# CC_microcontroleur.net
KiCad netlist of a schematic drawn in Altium Designer
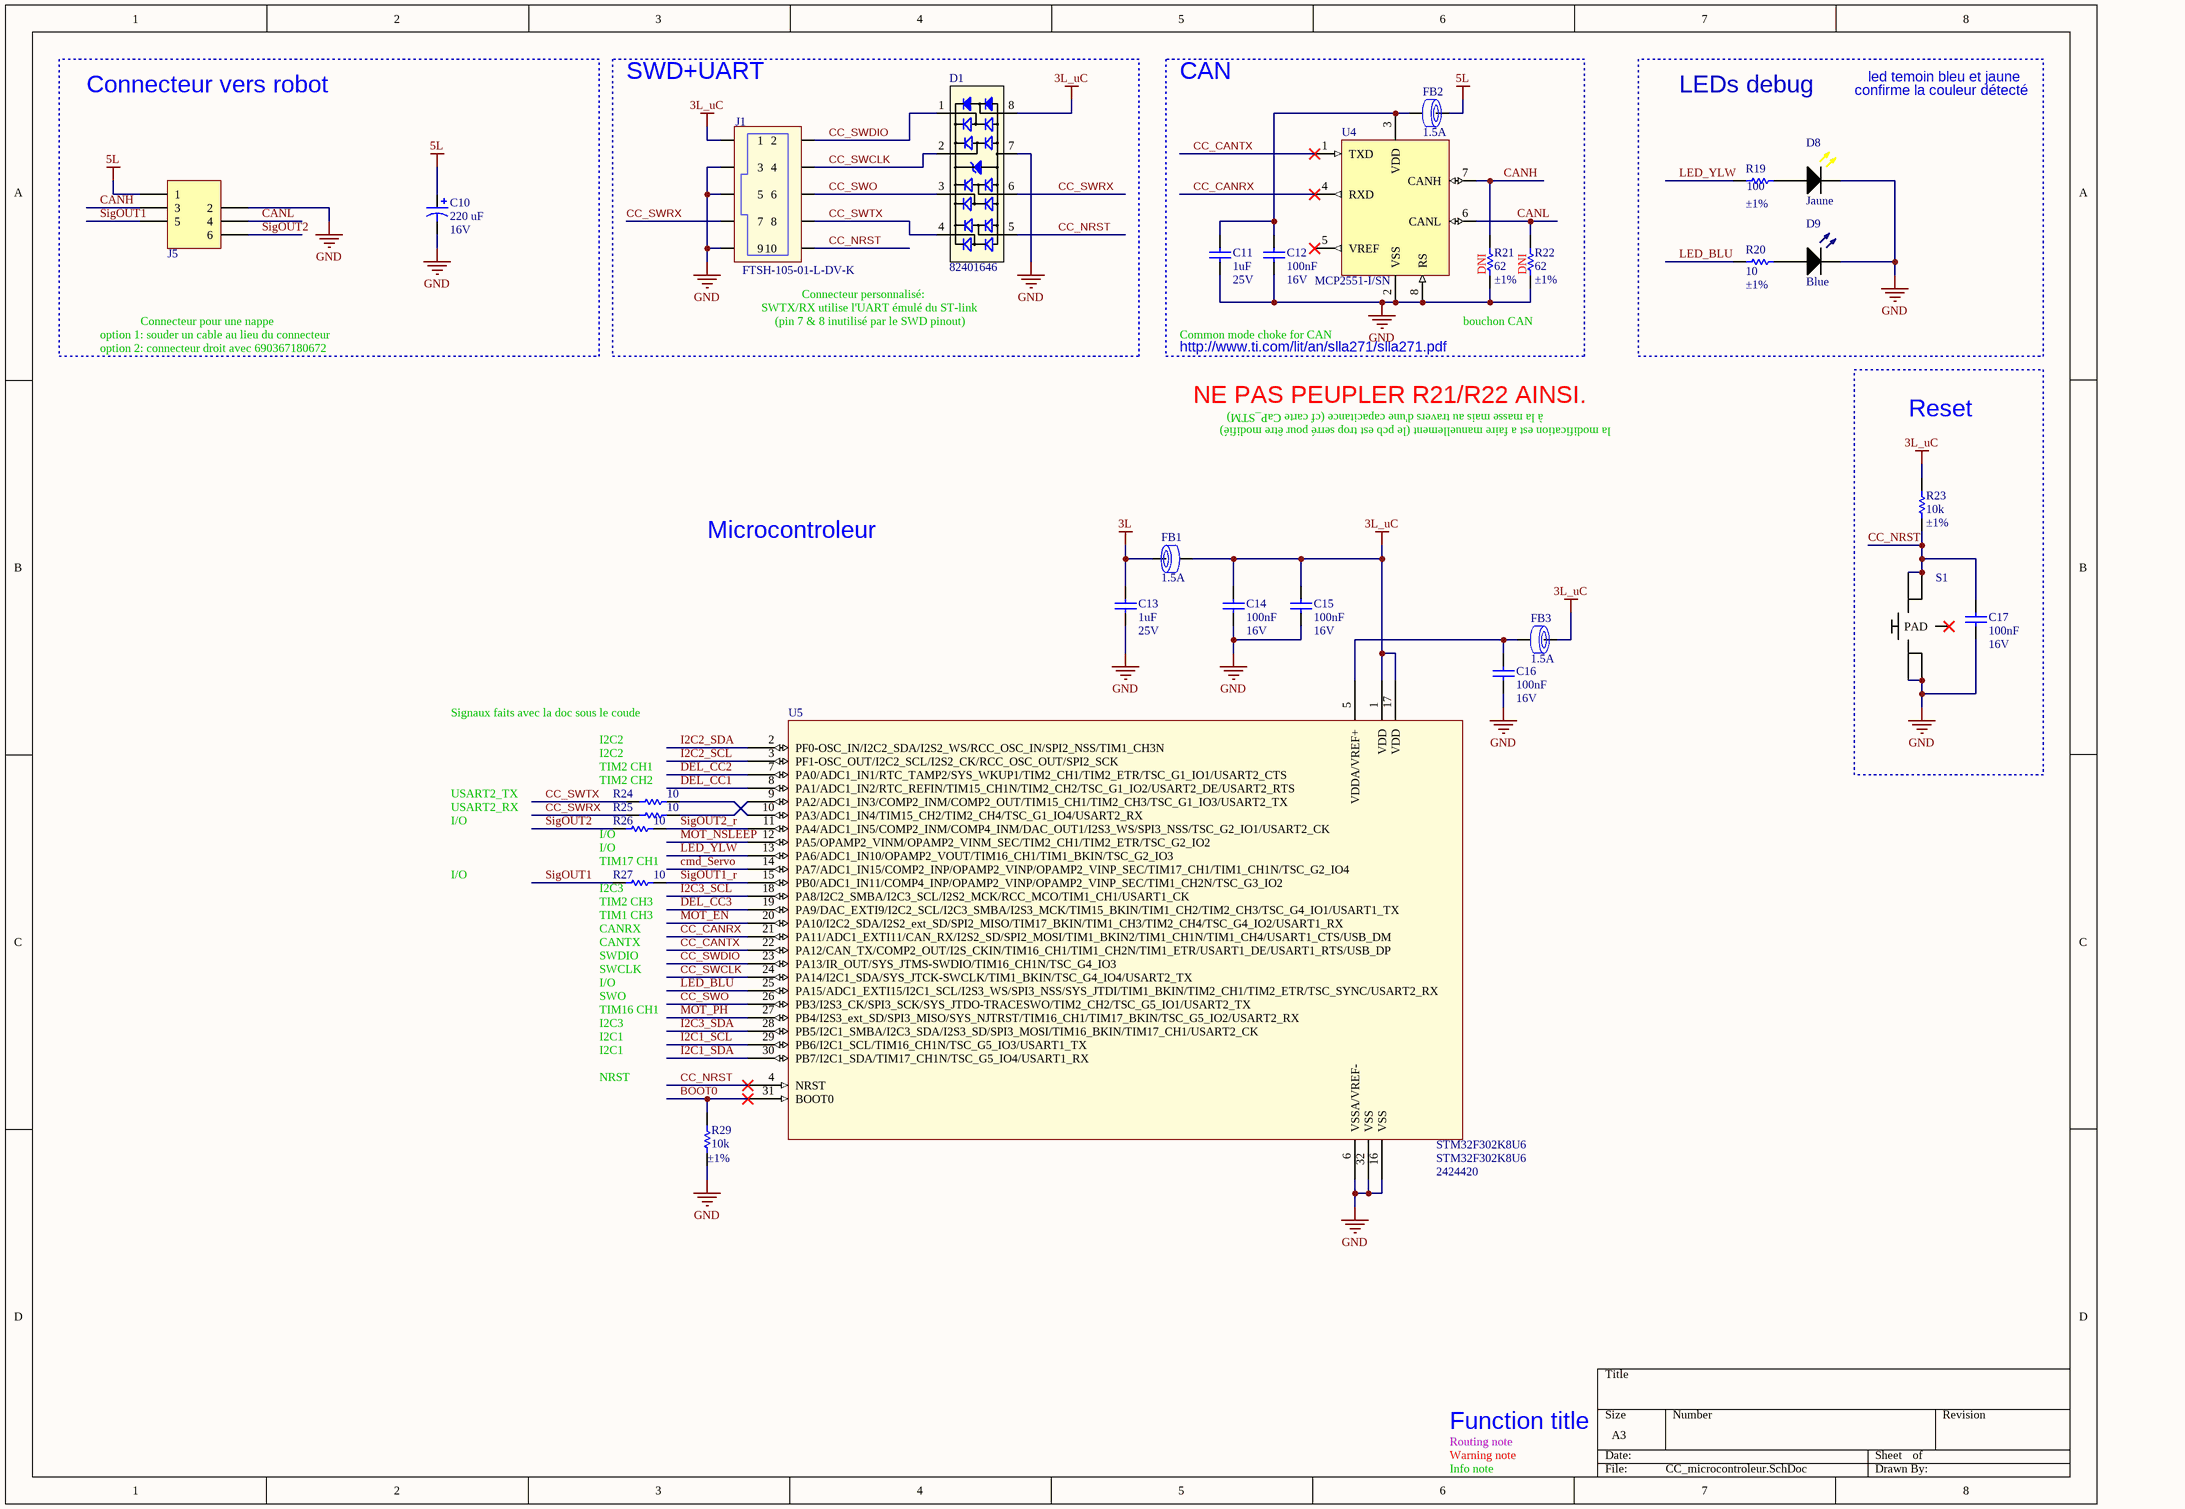
[diagram p0: CC_microcontroleur.SchDoc]

(export (version "E")
  (design (tool "Eeschema 10.0.6"))
  (components
    (comp (ref "C10")
      (value "220 uF")
      (footprint "WCAP-ATG8_6.3x11x2.5x0.5")
      (description "CAP Alu 220 UF 20% 16 V")
      (fields
        (field (name "MANUFACTURER") "Wurth Elektronik")
        (field (name "MANUFACTURER PART NUMBER") "860010373010")
        (field (name "RATEDVOLTAGE") "16V")
      )
      (libsource (lib "Condensateur") (part "WCAP-ATG8, 860010373010"))
    )
    (comp (ref "C11")
      (value "1uF")
      (footprint "WCAP-CSGP_0603, 1.6x0.8x0.8")
      (description "CAP CER 1uF 25V X7R 0603")
      (fields
        (field (name "MANUFACTURER") "Wurth Elektronik")
        (field (name "MANUFACTURER PART NUMBER") "885012206076")
        (field (name "RATEDVOLTAGE") "25V")
      )
      (libsource (lib "Condensateur") (part "WCAP-CSGP, 885012206076"))
    )
    (comp (ref "C12")
      (value "100nF")
      (footprint "WCAP-CSGP_0402, 1x0.5x0.5")
      (description "CAP CER 100nF 16V X7R 0402")
      (fields
        (field (name "RATEDVOLTAGE") "16V")
        (field (name "MANUFACTURER") "Wurth Elektronik")
        (field (name "MANUFACTURER PART NUMBER") "885012205037")
      )
      (libsource (lib "Condensateur") (part "WCAP-CSGP, 885012205037"))
    )
    (comp (ref "C13")
      (value "1uF")
      (footprint "WCAP-CSGP_0603, 1.6x0.8x0.8")
      (description "CAP CER 1uF 25V X7R 0603")
      (fields
        (field (name "MANUFACTURER") "Wurth Elektronik")
        (field (name "MANUFACTURER PART NUMBER") "885012206076")
        (field (name "RATEDVOLTAGE") "25V")
      )
      (libsource (lib "Condensateur") (part "WCAP-CSGP, 885012206076"))
    )
    (comp (ref "C14")
      (value "100nF")
      (footprint "WCAP-CSGP_0402, 1x0.5x0.5")
      (description "CAP CER 100nF 16V X7R 0402")
      (fields
        (field (name "RATEDVOLTAGE") "16V")
        (field (name "MANUFACTURER") "Wurth Elektronik")
        (field (name "MANUFACTURER PART NUMBER") "885012205037")
      )
      (libsource (lib "Condensateur") (part "WCAP-CSGP, 885012205037"))
    )
    (comp (ref "C15")
      (value "100nF")
      (footprint "WCAP-CSGP_0402, 1x0.5x0.5")
      (description "CAP CER 100nF 16V X7R 0402")
      (fields
        (field (name "RATEDVOLTAGE") "16V")
        (field (name "MANUFACTURER") "Wurth Elektronik")
        (field (name "MANUFACTURER PART NUMBER") "885012205037")
      )
      (libsource (lib "Condensateur") (part "WCAP-CSGP, 885012205037"))
    )
    (comp (ref "C16")
      (value "100nF")
      (footprint "WCAP-CSGP_0402, 1x0.5x0.5")
      (description "CAP CER 100nF 16V X7R 0402")
      (fields
        (field (name "RATEDVOLTAGE") "16V")
        (field (name "MANUFACTURER") "Wurth Elektronik")
        (field (name "MANUFACTURER PART NUMBER") "885012205037")
      )
      (libsource (lib "Condensateur") (part "WCAP-CSGP, 885012205037"))
    )
    (comp (ref "C17")
      (value "100nF")
      (footprint "WCAP-CSGP_0402, 1x0.5x0.5")
      (description "CAP CER 100nF 16V X7R 0402")
      (fields
        (field (name "MANUFACTURER") "Wurth Elektronik")
        (field (name "MANUFACTURER PART NUMBER") "885012205037")
        (field (name "RATEDVOLTAGE") "16V")
      )
      (libsource (lib "Condensateur") (part "WCAP-CSGP, 885012205037"))
    )
    (comp (ref "D1")
      (value "82401646")
      (footprint "MSOP-8L")
      (description "TVS DIODE 5VWM 13VC 8MSOP")
      (fields (field (name "MANUFACTURER") "Wurth Electronics Inc."))
      (libsource (lib "Diode") (part "82401646"))
    )
    (comp (ref "D8")
      (value "Jaune")
      (footprint "0603")
      (description "SMD mono-color Chip LED, WL-SMCW, Yellow")
      (fields
        (field (name "MANUFACTURER PART NUMBER") "150060YS75000")
        (field (name "CREATED BY") "Christin Otto")
      )
      (libsource (lib "Optoélectronique") (part "WL-SMCW 0603  150060YS75000"))
    )
    (comp (ref "D9")
      (value "Blue")
      (footprint "0603")
      (description "SMD mono-color Chip LED, WL-SMCW, Blue")
      (fields
        (field (name "MANUFACTURER PART NUMBER") "150060BS75000")
        (field (name "CREATED BY") "Christin Otto")
      )
      (libsource (lib "Optoélectronique") (part "WL-SMCW 0603  150060BS75000"))
    )
    (comp (ref "FB1")
      (value "742792624")
      (footprint "WE-CBF_0603_High Current")
      (description "Ferrite Bead 180ohm 0603 max1.5A")
      (fields (field (name "MANUFACTURER") "Wurth Elektronik") (field (name "RATEDCURRENT") "1.5A"))
      (libsource (lib "Inductance") (part "WE-CBF, 742792624"))
    )
    (comp (ref "FB2")
      (value "742792624")
      (footprint "WE-CBF_0603_High Current")
      (description "Ferrite Bead 180ohm 0603 max1.5A")
      (fields (field (name "MANUFACTURER") "Wurth Elektronik") (field (name "RATEDCURRENT") "1.5A"))
      (libsource (lib "Inductance") (part "WE-CBF, 742792624"))
    )
    (comp (ref "FB3")
      (value "742792624")
      (footprint "WE-CBF_0603_High Current")
      (description "Ferrite Bead 180ohm 0603 max1.5A")
      (fields (field (name "MANUFACTURER") "Wurth Elektronik") (field (name "RATEDCURRENT") "1.5A"))
      (libsource (lib "") (part "WE-CBF, 742792624_1"))
    )
    (comp (ref "J1")
      (value "FTSH-105-01-L-DV-K")
      (footprint "FTSH-105-01-L-DV-K")
      (description "CONN HEADER 10 POS DUAL .05\" SMD with Keying")
      (fields (field (name "MANUFACTURER") "Samtec Inc."))
      (libsource (lib "Connecteurs") (part "FTSH-105-01-L-DV-K"))
    )
    (comp (ref "J5")
      (value "690368170672")
      (footprint "690368170672")
      (description "WR-MM 6p Female Angled TH Connector with Polarization")
      (fields (field (name "MANUFACTURER") "Wurth Electronics Inc."))
      (libsource (lib "Connecteurs") (part "690368170672"))
    )
    (comp (ref "R19")
      (value "100")
      (footprint "RESC1005X04N")
      (description "RES SMD 100 OHM 1% 1/16W 0402")
      (fields
        (field (name "POWER") "63mW")
        (field (name "MANUFACTURER") "Yageo")
        (field (name "PRECISION") "±1%")
      )
      (libsource (lib "Resistance") (part "RC0402FR-07100RL"))
    )
    (comp (ref "R20")
      (value "10")
      (footprint "RESC1005X04N")
      (description "RES SMD 10 OHM 1% 1/16W 0402")
      (fields
        (field (name "POWER") "63mW")
        (field (name "MANUFACTURER") "Yageo")
        (field (name "PRECISION") "±1%")
      )
      (libsource (lib "Resistance") (part "RC0402FR-0710RL"))
    )
    (comp (ref "R21")
      (value "62")
      (footprint "RESC1005X04N")
      (description "RES SMD 62 OHM 1% 1/16W 0402")
      (fields
        (field (name "POWER") "63mW")
        (field (name "MANUFACTURER") "Yageo")
        (field (name "PRECISION") "±1%")
      )
      (libsource (lib "Resistance") (part "RC0402FR-0762RL"))
    )
    (comp (ref "R22")
      (value "62")
      (footprint "RESC1005X04N")
      (description "RES SMD 62 OHM 1% 1/16W 0402")
      (fields
        (field (name "POWER") "63mW")
        (field (name "MANUFACTURER") "Yageo")
        (field (name "PRECISION") "±1%")
      )
      (libsource (lib "Resistance") (part "RC0402FR-0762RL"))
    )
    (comp (ref "R23")
      (value "10k")
      (footprint "RESC1005X04N")
      (description "RES SMD 10K OHM 1% 1/16W 0402")
      (fields
        (field (name "POWER") "63mW")
        (field (name "MANUFACTURER") "Yageo")
        (field (name "PRECISION") "±1%")
      )
      (libsource (lib "Resistance") (part "RC0402FR-0710KL"))
    )
    (comp (ref "R24")
      (value "10")
      (footprint "RESC1005X04N")
      (description "RES SMD 10 OHM 1% 1/16W 0402")
      (fields (field (name "POWER") "63mW") (field (name "MANUFACTURER") "Yageo"))
      (libsource (lib "Resistance") (part "RC0402FR-0710RL"))
    )
    (comp (ref "R25")
      (value "10")
      (footprint "RESC1005X04N")
      (description "RES SMD 10 OHM 1% 1/16W 0402")
      (fields (field (name "POWER") "63mW") (field (name "MANUFACTURER") "Yageo"))
      (libsource (lib "Resistance") (part "RC0402FR-0710RL"))
    )
    (comp (ref "R26")
      (value "10")
      (footprint "RESC1005X04N")
      (description "RES SMD 10 OHM 1% 1/16W 0402")
      (fields (field (name "POWER") "63mW") (field (name "MANUFACTURER") "Yageo"))
      (libsource (lib "Resistance") (part "RC0402FR-0710RL"))
    )
    (comp (ref "R27")
      (value "10")
      (footprint "RESC1005X04N")
      (description "RES SMD 10 OHM 1% 1/16W 0402")
      (fields (field (name "POWER") "63mW") (field (name "MANUFACTURER") "Yageo"))
      (libsource (lib "Resistance") (part "RC0402FR-0710RL"))
    )
    (comp (ref "R29")
      (value "10k")
      (footprint "RESC1005X04N")
      (description "RES SMD 10K OHM 1% 1/16W 0402")
      (fields
        (field (name "POWER") "63mW")
        (field (name "MANUFACTURER") "Yageo")
        (field (name "PRECISION") "±1%")
      )
      (libsource (lib "Resistance") (part "RC0402FR-0710KL"))
    )
    (comp (ref "S1")
      (value "MCITPG")
      (footprint "MCIPTG23K-V")
      (description "Switch MCIPTG23K-V Multicomp")
      (fields
        (field (name "MANUFACTURER") "MULTICOMP")
        (field (name "MANUFACTURER PART NUMBER") "MCIPTG23K-V")
      )
      (libsource (lib "Switchs") (part "MCIPTG23K-V"))
    )
    (comp (ref "U4")
      (value "MCP2551-I/SN")
      (footprint "SO8_N")
      (description "IC TRANSCEIVER CAN HI-SPD 8-SOIC")
      (fields (field (name "MANUFACTURER") "Microchip Technology"))
      (libsource (lib "Serial") (part "MCP2551-I/SN"))
    )
    (comp (ref "U5")
      (value "STM32F302K8U6")
      (footprint "QFN50P500X500X60_HS-33N")
      (fields
        (field (name "MANUFACTURER") "STMICROELECTRONICS")
        (field (name "MANUFACTURER PART NUMBER") "STM32F302K8U6")
        (field (name "SUPPLIER PART NUMBER 1") "2424420")
      )
      (libsource (lib "Stm32") (part "STM32F302K8U6"))
    )
  )
  (nets
    (net (code "1") (name "/BOOT0") (class "Default")
      (node (ref "R29") (pin "2") (pinfunction "2_2") (pintype "passive"))
      (node (ref "U5") (pin "31") (pinfunction "BOOT0_31") (pintype "input"))
    )
    (net (code "2") (name "/CANH") (class "Default")
      (node (ref "J5") (pin "3") (pinfunction "3_3") (pintype "passive"))
      (node (ref "R21") (pin "2") (pinfunction "2_2") (pintype "passive"))
      (node (ref "U4") (pin "7") (pinfunction "CANH_7") (pintype "bidirectional"))
    )
    (net (code "3") (name "/CANL") (class "Default")
      (node (ref "J5") (pin "4") (pinfunction "4_4") (pintype "passive"))
      (node (ref "R22") (pin "2") (pinfunction "2_2") (pintype "passive"))
      (node (ref "U4") (pin "6") (pinfunction "CANL_6") (pintype "bidirectional"))
    )
    (net (code "4") (name "/CC_CANRX") (class "Default")
      (node (ref "U4") (pin "4") (pinfunction "RXD_4") (pintype "output"))
      (node (ref "U5") (pin "21") (pinfunction "PA11/ADC1_EXTI11/CAN_RX/I2S2_SD/SPI2_MOSI/TIM1_BKIN2/TIM1_CH1N/TIM1_CH4/USART1_CTS/USB_DM_21") (pintype "bidirectional"))
    )
    (net (code "5") (name "/CC_CANTX") (class "Default")
      (node (ref "U4") (pin "1") (pinfunction "TXD_1") (pintype "input"))
      (node (ref "U5") (pin "22") (pinfunction "PA12/CAN_TX/COMP2_OUT/I2S_CKIN/TIM16_CH1/TIM1_CH2N/TIM1_ETR/USART1_DE/USART1_RTS/USB_DP_22") (pintype "bidirectional"))
    )
    (net (code "6") (name "/CC_NRST") (class "Default")
      (node (ref "C17") (pin "2") (pinfunction "2_2") (pintype "passive"))
      (node (ref "D1") (pin "5") (pintype "passive"))
      (node (ref "J1") (pin "10") (pinfunction "10_10") (pintype "passive"))
      (node (ref "R23") (pin "1") (pinfunction "1_1") (pintype "passive"))
      (node (ref "S1") (pin "2") (pinfunction "2_2") (pintype "passive"))
      (node (ref "S1") (pin "4") (pinfunction "4_4") (pintype "passive"))
      (node (ref "U5") (pin "4") (pinfunction "NRST_4") (pintype "input"))
    )
    (net (code "7") (name "/CC_SWCLK") (class "Default")
      (node (ref "D1") (pin "2") (pintype "passive"))
      (node (ref "J1") (pin "4") (pinfunction "4_4") (pintype "passive"))
      (node (ref "U5") (pin "24") (pinfunction "PA14/I2C1_SDA/SYS_JTCK-SWCLK/TIM1_BKIN/TSC_G4_IO4/USART2_TX_24") (pintype "bidirectional"))
    )
    (net (code "8") (name "/CC_SWDIO") (class "Default")
      (node (ref "D1") (pin "1") (pintype "passive"))
      (node (ref "J1") (pin "2") (pinfunction "2_2") (pintype "passive"))
      (node (ref "U5") (pin "23") (pinfunction "PA13/IR_OUT/SYS_JTMS-SWDIO/TIM16_CH1N/TSC_G4_IO3_23") (pintype "bidirectional"))
    )
    (net (code "9") (name "/CC_SWO") (class "Default")
      (node (ref "D1") (pin "3") (pintype "passive"))
      (node (ref "J1") (pin "6") (pinfunction "6_6") (pintype "passive"))
      (node (ref "U5") (pin "26") (pinfunction "PB3/I2S3_CK/SPI3_SCK/SYS_JTDO-TRACESWO/TIM2_CH2/TSC_G5_IO1/USART2_TX_26") (pintype "bidirectional"))
    )
    (net (code "10") (name "/CC_SWRX") (class "Default")
      (node (ref "D1") (pin "6") (pintype "passive"))
      (node (ref "J1") (pin "7") (pinfunction "7_7") (pintype "passive"))
      (node (ref "R25") (pin "1") (pinfunction "1_1") (pintype "passive"))
    )
    (net (code "11") (name "/CC_SWTX") (class "Default")
      (node (ref "D1") (pin "4") (pintype "passive"))
      (node (ref "J1") (pin "8") (pinfunction "8_8") (pintype "passive"))
      (node (ref "R24") (pin "1") (pinfunction "1_1") (pintype "passive"))
    )
    (net (code "12") (name "/DEL_CC1") (class "Default")
      (node (ref "U5") (pin "8") (pinfunction "PA1/ADC1_IN2/RTC_REFIN/TIM15_CH1N/TIM2_CH2/TSC_G1_IO2/USART2_DE/USART2_RTS_8") (pintype "bidirectional"))
    )
    (net (code "13") (name "/DEL_CC2") (class "Default")
      (node (ref "U5") (pin "7") (pinfunction "PA0/ADC1_IN1/RTC_TAMP2/SYS_WKUP1/TIM2_CH1/TIM2_ETR/TSC_G1_IO1/USART2_CTS_7") (pintype "bidirectional"))
    )
    (net (code "14") (name "/DEL_CC3") (class "Default")
      (node (ref "U5") (pin "19") (pinfunction "PA9/DAC_EXTI9/I2C2_SCL/I2C3_SMBA/I2S3_MCK/TIM15_BKIN/TIM1_CH2/TIM2_CH3/TSC_G4_IO1/USART1_TX_19") (pintype "bidirectional"))
    )
    (net (code "15") (name "/I2C1_SCL") (class "Default")
      (node (ref "U5") (pin "29") (pinfunction "PB6/I2C1_SCL/TIM16_CH1N/TSC_G5_IO3/USART1_TX_29") (pintype "bidirectional"))
    )
    (net (code "16") (name "/I2C1_SDA") (class "Default")
      (node (ref "U5") (pin "30") (pinfunction "PB7/I2C1_SDA/TIM17_CH1N/TSC_G5_IO4/USART1_RX_30") (pintype "bidirectional"))
    )
    (net (code "17") (name "/I2C2_SCL") (class "Default")
      (node (ref "U5") (pin "3") (pinfunction "PF1-OSC_OUT/I2C2_SCL/I2S2_CK/RCC_OSC_OUT/SPI2_SCK_3") (pintype "bidirectional"))
    )
    (net (code "18") (name "/I2C2_SDA") (class "Default")
      (node (ref "U5") (pin "2") (pinfunction "PF0-OSC_IN/I2C2_SDA/I2S2_WS/RCC_OSC_IN/SPI2_NSS/TIM1_CH3N_2") (pintype "bidirectional"))
    )
    (net (code "19") (name "/I2C3_SCL") (class "Default")
      (node (ref "U5") (pin "18") (pinfunction "PA8/I2C2_SMBA/I2C3_SCL/I2S2_MCK/RCC_MCO/TIM1_CH1/USART1_CK_18") (pintype "bidirectional"))
    )
    (net (code "20") (name "/I2C3_SDA") (class "Default")
      (node (ref "U5") (pin "28") (pinfunction "PB5/I2C1_SMBA/I2C3_SDA/I2S3_SD/SPI3_MOSI/TIM16_BKIN/TIM17_CH1/USART2_CK_28") (pintype "bidirectional"))
    )
    (net (code "21") (name "/LED_BLU") (class "Default")
      (node (ref "R20") (pin "1") (pinfunction "1_1") (pintype "passive"))
      (node (ref "U5") (pin "25") (pinfunction "PA15/ADC1_EXTI15/I2C1_SCL/I2S3_WS/SPI3_NSS/SYS_JTDI/TIM1_BKIN/TIM2_CH1/TIM2_ETR/TSC_SYNC/USART2_RX_25") (pintype "bidirectional"))
    )
    (net (code "22") (name "/LED_YLW") (class "Default")
      (node (ref "R19") (pin "1") (pinfunction "1_1") (pintype "passive"))
      (node (ref "U5") (pin "13") (pinfunction "PA6/ADC1_IN10/OPAMP2_VOUT/TIM16_CH1/TIM1_BKIN/TSC_G2_IO3_13") (pintype "bidirectional"))
    )
    (net (code "23") (name "/MOT_EN") (class "Default")
      (node (ref "U5") (pin "20") (pinfunction "PA10/I2C2_SDA/I2S2_ext_SD/SPI2_MISO/TIM17_BKIN/TIM1_CH3/TIM2_CH4/TSC_G4_IO2/USART1_RX_20") (pintype "bidirectional"))
    )
    (net (code "24") (name "/MOT_NSLEEP") (class "Default")
      (node (ref "U5") (pin "12") (pinfunction "PA5/OPAMP2_VINM/OPAMP2_VINM_SEC/TIM2_CH1/TIM2_ETR/TSC_G2_IO2_12") (pintype "bidirectional"))
    )
    (net (code "25") (name "/MOT_PH") (class "Default")
      (node (ref "U5") (pin "27") (pinfunction "PB4/I2S3_ext_SD/SPI3_MISO/SYS_NJTRST/TIM16_CH1/TIM17_BKIN/TSC_G5_IO2/USART2_RX_27") (pintype "bidirectional"))
    )
    (net (code "26") (name "/SigOUT1") (class "Default")
      (node (ref "J5") (pin "5") (pinfunction "5_5") (pintype "passive"))
      (node (ref "R27") (pin "1") (pinfunction "1_1") (pintype "passive"))
    )
    (net (code "27") (name "/SigOUT1_r") (class "Default")
      (node (ref "R27") (pin "2") (pinfunction "2_2") (pintype "passive"))
      (node (ref "U5") (pin "15") (pinfunction "PB0/ADC1_IN11/COMP4_INP/OPAMP2_VINP/OPAMP2_VINP_SEC/TIM1_CH2N/TSC_G3_IO2_15") (pintype "bidirectional"))
    )
    (net (code "28") (name "/SigOUT2") (class "Default")
      (node (ref "J5") (pin "6") (pinfunction "6_6") (pintype "passive"))
      (node (ref "R26") (pin "1") (pinfunction "1_1") (pintype "passive"))
    )
    (net (code "29") (name "/SigOUT2_r") (class "Default")
      (node (ref "R26") (pin "2") (pinfunction "2_2") (pintype "passive"))
      (node (ref "U5") (pin "11") (pinfunction "PA4/ADC1_IN5/COMP2_INM/COMP4_INM/DAC_OUT1/I2S3_WS/SPI3_NSS/TSC_G2_IO1/USART2_CK_11") (pintype "bidirectional"))
    )
    (net (code "30") (name "/cmd_Servo") (class "Default")
      (node (ref "U5") (pin "14") (pinfunction "PA7/ADC1_IN15/COMP2_INP/OPAMP2_VINP/OPAMP2_VINP_SEC/TIM17_CH1/TIM1_CH1N/TSC_G2_IO4_14") (pintype "bidirectional"))
    )
    (net (code "31") (name "3L") (class "Default")
      (node (ref "C13") (pin "2") (pinfunction "2_2") (pintype "passive"))
      (node (ref "FB1") (pin "1") (pinfunction "1_1") (pintype "passive"))
    )
    (net (code "32") (name "3L_uC") (class "Default")
      (node (ref "C14") (pin "2") (pinfunction "2_2") (pintype "passive"))
      (node (ref "C15") (pin "2") (pinfunction "2_2") (pintype "passive"))
      (node (ref "D1") (pin "8") (pintype "passive"))
      (node (ref "FB1") (pin "2") (pinfunction "2_2") (pintype "passive"))
      (node (ref "FB3") (pin "1") (pinfunction "1_1") (pintype "passive"))
      (node (ref "J1") (pin "1") (pinfunction "1_1") (pintype "passive"))
      (node (ref "R23") (pin "2") (pinfunction "2_2") (pintype "passive"))
      (node (ref "U5") (pin "1") (pinfunction "VDD_1") (pintype "power_in"))
      (node (ref "U5") (pin "17") (pinfunction "VDD_17") (pintype "power_in"))
    )
    (net (code "33") (name "5L") (class "Default")
      (node (ref "C10") (pin "1") (pinfunction "1_1") (pintype "passive"))
      (node (ref "FB2") (pin "1") (pinfunction "1_1") (pintype "passive"))
      (node (ref "J5") (pin "1") (pinfunction "1_1") (pintype "passive"))
    )
    (net (code "34") (name "GND") (class "Default")
      (node (ref "C10") (pin "2") (pinfunction "2_2") (pintype "passive"))
      (node (ref "C11") (pin "1") (pinfunction "1_1") (pintype "passive"))
      (node (ref "C12") (pin "1") (pinfunction "1_1") (pintype "passive"))
      (node (ref "C13") (pin "1") (pinfunction "1_1") (pintype "passive"))
      (node (ref "C14") (pin "1") (pinfunction "1_1") (pintype "passive"))
      (node (ref "C15") (pin "1") (pinfunction "1_1") (pintype "passive"))
      (node (ref "C16") (pin "1") (pinfunction "1_1") (pintype "passive"))
      (node (ref "C17") (pin "1") (pinfunction "1_1") (pintype "passive"))
      (node (ref "D1") (pin "7") (pintype "passive"))
      (node (ref "D8") (pin "1") (pinfunction "C_1") (pintype "passive"))
      (node (ref "D9") (pin "1") (pinfunction "C_1") (pintype "passive"))
      (node (ref "J1") (pin "3") (pinfunction "3_3") (pintype "passive"))
      (node (ref "J1") (pin "5") (pinfunction "5_5") (pintype "passive"))
      (node (ref "J1") (pin "9") (pinfunction "9_9") (pintype "passive"))
      (node (ref "J5") (pin "2") (pinfunction "2_2") (pintype "passive"))
      (node (ref "R21") (pin "1") (pinfunction "1_1") (pintype "passive"))
      (node (ref "R22") (pin "1") (pinfunction "1_1") (pintype "passive"))
      (node (ref "R29") (pin "1") (pinfunction "1_1") (pintype "passive"))
      (node (ref "S1") (pin "1") (pinfunction "1_1") (pintype "passive"))
      (node (ref "S1") (pin "3") (pinfunction "3_3") (pintype "passive"))
      (node (ref "U4") (pin "2") (pinfunction "VSS_2") (pintype "power_in"))
      (node (ref "U4") (pin "8") (pinfunction "RS_8") (pintype "input"))
      (node (ref "U5") (pin "16") (pinfunction "VSS_16") (pintype "power_in"))
      (node (ref "U5") (pin "32") (pinfunction "VSS_32") (pintype "power_in"))
      (node (ref "U5") (pin "6") (pinfunction "VSSA/VREF-_6") (pintype "power_in"))
    )
    (net (code "35") (name "Net-(D8-A)") (class "Default")
      (node (ref "D8") (pin "2") (pinfunction "A_2") (pintype "passive"))
      (node (ref "R19") (pin "2") (pinfunction "2_2") (pintype "passive"))
    )
    (net (code "36") (name "Net-(D9-A)") (class "Default")
      (node (ref "D9") (pin "2") (pinfunction "A_2") (pintype "passive"))
      (node (ref "R20") (pin "2") (pinfunction "2_2") (pintype "passive"))
    )
    (net (code "37") (name "Net-(U4-VDD)") (class "Default")
      (node (ref "C11") (pin "2") (pinfunction "2_2") (pintype "passive"))
      (node (ref "C12") (pin "2") (pinfunction "2_2") (pintype "passive"))
      (node (ref "FB2") (pin "2") (pinfunction "2_2") (pintype "passive"))
      (node (ref "U4") (pin "3") (pinfunction "VDD_3") (pintype "power_in"))
    )
    (net (code "38") (name "Net-(U5-PA2{slash}ADC1_IN3{slash}COMP2_INM{slash}COMP2_OUT{slash}TIM15_CH1{slash}TIM2_CH3{slash}TSC_G1_IO3{slash}USART2_TX)") (class "Default")
      (node (ref "R25") (pin "2") (pinfunction "2_2") (pintype "passive"))
      (node (ref "U5") (pin "9") (pinfunction "PA2/ADC1_IN3/COMP2_INM/COMP2_OUT/TIM15_CH1/TIM2_CH3/TSC_G1_IO3/USART2_TX_9") (pintype "bidirectional"))
    )
    (net (code "39") (name "Net-(U5-PA3{slash}ADC1_IN4{slash}TIM15_CH2{slash}TIM2_CH4{slash}TSC_G1_IO4{slash}USART2_RX)") (class "Default")
      (node (ref "R24") (pin "2") (pinfunction "2_2") (pintype "passive"))
      (node (ref "U5") (pin "10") (pinfunction "PA3/ADC1_IN4/TIM15_CH2/TIM2_CH4/TSC_G1_IO4/USART2_RX_10") (pintype "bidirectional"))
    )
    (net (code "40") (name "Net-(U5-VDDA{slash}VREF+)") (class "Default")
      (node (ref "C16") (pin "2") (pinfunction "2_2") (pintype "passive"))
      (node (ref "FB3") (pin "2") (pinfunction "2_2") (pintype "passive"))
      (node (ref "U5") (pin "5") (pinfunction "VDDA/VREF+_5") (pintype "power_in"))
    )
    (net (code "41") (name "unconnected-(S1-PAD-Pad5)") (class "Default")
      (node (ref "S1") (pin "5") (pinfunction "PAD_5") (pintype "passive+no_connect"))
    )
    (net (code "42") (name "unconnected-(U4-VREF-Pad5)") (class "Default")
      (node (ref "U4") (pin "5") (pinfunction "VREF_5") (pintype "output+no_connect"))
    )
  )
)
